# FTDI_FT232.net
KiCad netlist of a schematic drawn in EAGLE
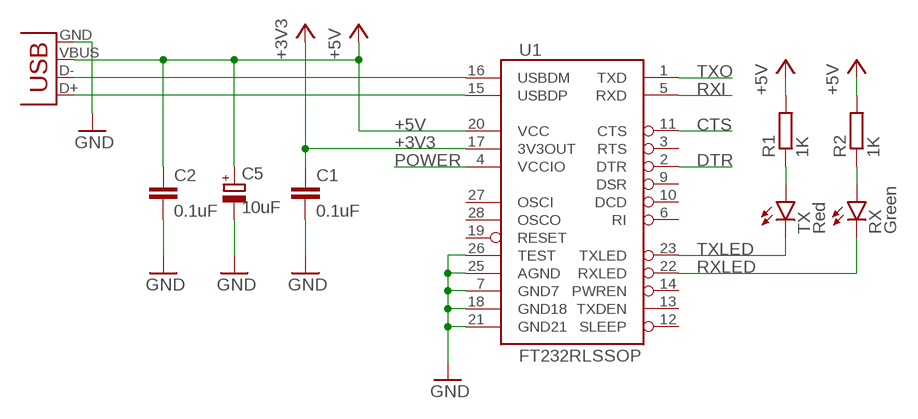
[diagram p0: schematic, sheet 1]

(export (version "E")
  (design (tool "Eeschema 10.0.6"))
  (components
    (comp (ref "C1")
      (value "0.1uF")
      (footprint "eagle-import:C0805")
      (libsource (lib "eagle-import") (part "C-EUC0805"))
    )
    (comp (ref "C2")
      (value "0.1uF")
      (footprint "eagle-import:C0805")
      (libsource (lib "eagle-import") (part "C-EUC0805"))
    )
    (comp (ref "C5")
      (value "10uF")
      (footprint "eagle-import:PANASONIC_B")
      (libsource (lib "eagle-import") (part "CPOL-EUB"))
    )
    (comp (ref "R1")
      (value "1K")
      (footprint "eagle-import:R0805")
      (libsource (lib "eagle-import") (part "R-EU_R0805"))
    )
    (comp (ref "R2")
      (value "1K")
      (footprint "eagle-import:R0805")
      (libsource (lib "eagle-import") (part "R-EU_R0805"))
    )
    (comp (ref "RX")
      (value "Green")
      (footprint "eagle-import:CHIPLED_0805")
      (libsource (lib "eagle-import") (part "LEDCHIPLED_0805"))
    )
    (comp (ref "TX")
      (value "Red")
      (footprint "eagle-import:CHIPLED_0805")
      (libsource (lib "eagle-import") (part "LEDCHIPLED_0805"))
    )
    (comp (ref "U1")
      (value "FT232RLSSOP")
      (footprint "eagle-import:SSOP28DB")
      (libsource (lib "eagle-import") (part "FT232RLSSOP"))
    )
    (comp (ref "X2")
      (value "USB-SMD-NS")
      (footprint "eagle-import:USB-MINIB-NOSTOP")
      (libsource (lib "eagle-import") (part "USB-SMD-NS"))
    )
  )
  (nets
    (net (code "1") (name "+3V3") (class "Default")
      (node (ref "C1") (pin "1") (pinfunction "1_1") (pintype "passive"))
      (node (ref "U1") (pin "17") (pinfunction "3V3OUT_17") (pintype "output"))
    )
    (net (code "2") (name "+5V") (class "Default")
      (node (ref "C2") (pin "1") (pinfunction "1_1") (pintype "passive"))
      (node (ref "C5") (pin "+") (pinfunction "+_+") (pintype "passive"))
      (node (ref "R1") (pin "2") (pinfunction "2_2") (pintype "passive"))
      (node (ref "R2") (pin "2") (pinfunction "2_2") (pintype "passive"))
      (node (ref "U1") (pin "20") (pinfunction "VCC_20") (pintype "power_in"))
      (node (ref "X2") (pin "VBUS") (pinfunction "VBUS_VBUS") (pintype "bidirectional"))
    )
    (net (code "3") (name "/CTS") (class "Default")
      (node (ref "U1") (pin "11") (pinfunction "CTS_11") (pintype "input"))
    )
    (net (code "4") (name "/DTR") (class "Default")
      (node (ref "U1") (pin "2") (pinfunction "DTR_2") (pintype "output"))
    )
    (net (code "5") (name "/POWER") (class "Default")
      (node (ref "U1") (pin "4") (pinfunction "VCCIO_4") (pintype "power_in"))
    )
    (net (code "6") (name "/RXI") (class "Default")
      (node (ref "U1") (pin "5") (pinfunction "RXD_5") (pintype "input"))
    )
    (net (code "7") (name "/RXLED") (class "Default")
      (node (ref "RX") (pin "C") (pinfunction "C_C") (pintype "passive"))
      (node (ref "U1") (pin "22") (pinfunction "RXLED_22") (pintype "input"))
    )
    (net (code "8") (name "/TXLED") (class "Default")
      (node (ref "TX") (pin "C") (pinfunction "C_C") (pintype "passive"))
      (node (ref "U1") (pin "23") (pinfunction "TXLED_23") (pintype "input"))
    )
    (net (code "9") (name "/TXO") (class "Default")
      (node (ref "U1") (pin "1") (pinfunction "TXD_1") (pintype "output"))
    )
    (net (code "10") (name "GND") (class "Default")
      (node (ref "C1") (pin "2") (pinfunction "2_2") (pintype "passive"))
      (node (ref "C2") (pin "2") (pinfunction "2_2") (pintype "passive"))
      (node (ref "C5") (pin "-") (pinfunction "-_-") (pintype "passive"))
      (node (ref "U1") (pin "18") (pinfunction "GND18_18") (pintype "power_in"))
      (node (ref "U1") (pin "21") (pinfunction "GND21_21") (pintype "power_in"))
      (node (ref "U1") (pin "25") (pinfunction "AGND_25") (pintype "power_in"))
      (node (ref "U1") (pin "26") (pinfunction "TEST_26") (pintype "input"))
      (node (ref "U1") (pin "7") (pinfunction "GND7_7") (pintype "power_in"))
      (node (ref "X2") (pin "GND") (pinfunction "GND_GND") (pintype "bidirectional"))
    )
    (net (code "11") (name "Net-(R1-Pad1)") (class "Default")
      (node (ref "R1") (pin "1") (pinfunction "1_1") (pintype "passive"))
      (node (ref "TX") (pin "A") (pinfunction "A_A") (pintype "passive"))
    )
    (net (code "12") (name "Net-(R2-Pad1)") (class "Default")
      (node (ref "R2") (pin "1") (pinfunction "1_1") (pintype "passive"))
      (node (ref "RX") (pin "A") (pinfunction "A_A") (pintype "passive"))
    )
    (net (code "13") (name "Net-(U1-USBDM)") (class "Default")
      (node (ref "U1") (pin "16") (pinfunction "USBDM_16") (pintype "bidirectional"))
      (node (ref "X2") (pin "D-") (pinfunction "D-_D-") (pintype "bidirectional"))
    )
    (net (code "14") (name "Net-(U1-USBDP)") (class "Default")
      (node (ref "U1") (pin "15") (pinfunction "USBDP_15") (pintype "bidirectional"))
      (node (ref "X2") (pin "D+") (pinfunction "D+_D+") (pintype "bidirectional"))
    )
    (net (code "15") (name "unconnected-(U1-DCD-Pad10)") (class "Default")
      (node (ref "U1") (pin "10") (pinfunction "DCD_10") (pintype "input"))
    )
    (net (code "16") (name "unconnected-(U1-DSR-Pad9)") (class "Default")
      (node (ref "U1") (pin "9") (pinfunction "DSR_9") (pintype "input"))
    )
    (net (code "17") (name "unconnected-(U1-OSCI-Pad27)") (class "Default")
      (node (ref "U1") (pin "27") (pinfunction "OSCI_27") (pintype "input"))
    )
    (net (code "18") (name "unconnected-(U1-OSCO-Pad28)") (class "Default")
      (node (ref "U1") (pin "28") (pinfunction "OSCO_28") (pintype "output"))
    )
    (net (code "19") (name "unconnected-(U1-PWREN-Pad14)") (class "Default")
      (node (ref "U1") (pin "14") (pinfunction "PWREN_14") (pintype "input"))
    )
    (net (code "20") (name "unconnected-(U1-RESET-Pad19)") (class "Default")
      (node (ref "U1") (pin "19") (pinfunction "RESET_19") (pintype "input"))
    )
    (net (code "21") (name "unconnected-(U1-RI-Pad6)") (class "Default")
      (node (ref "U1") (pin "6") (pinfunction "RI_6") (pintype "input"))
    )
    (net (code "22") (name "unconnected-(U1-RTS-Pad3)") (class "Default")
      (node (ref "U1") (pin "3") (pinfunction "RTS_3") (pintype "output"))
    )
    (net (code "23") (name "unconnected-(U1-SLEEP-Pad12)") (class "Default")
      (node (ref "U1") (pin "12") (pinfunction "SLEEP_12") (pintype "input"))
    )
    (net (code "24") (name "unconnected-(U1-TXDEN-Pad13)") (class "Default")
      (node (ref "U1") (pin "13") (pinfunction "TXDEN_13") (pintype "input"))
    )
  )
)
